# power.net
KiCad netlist of a schematic drawn in Altium Designer
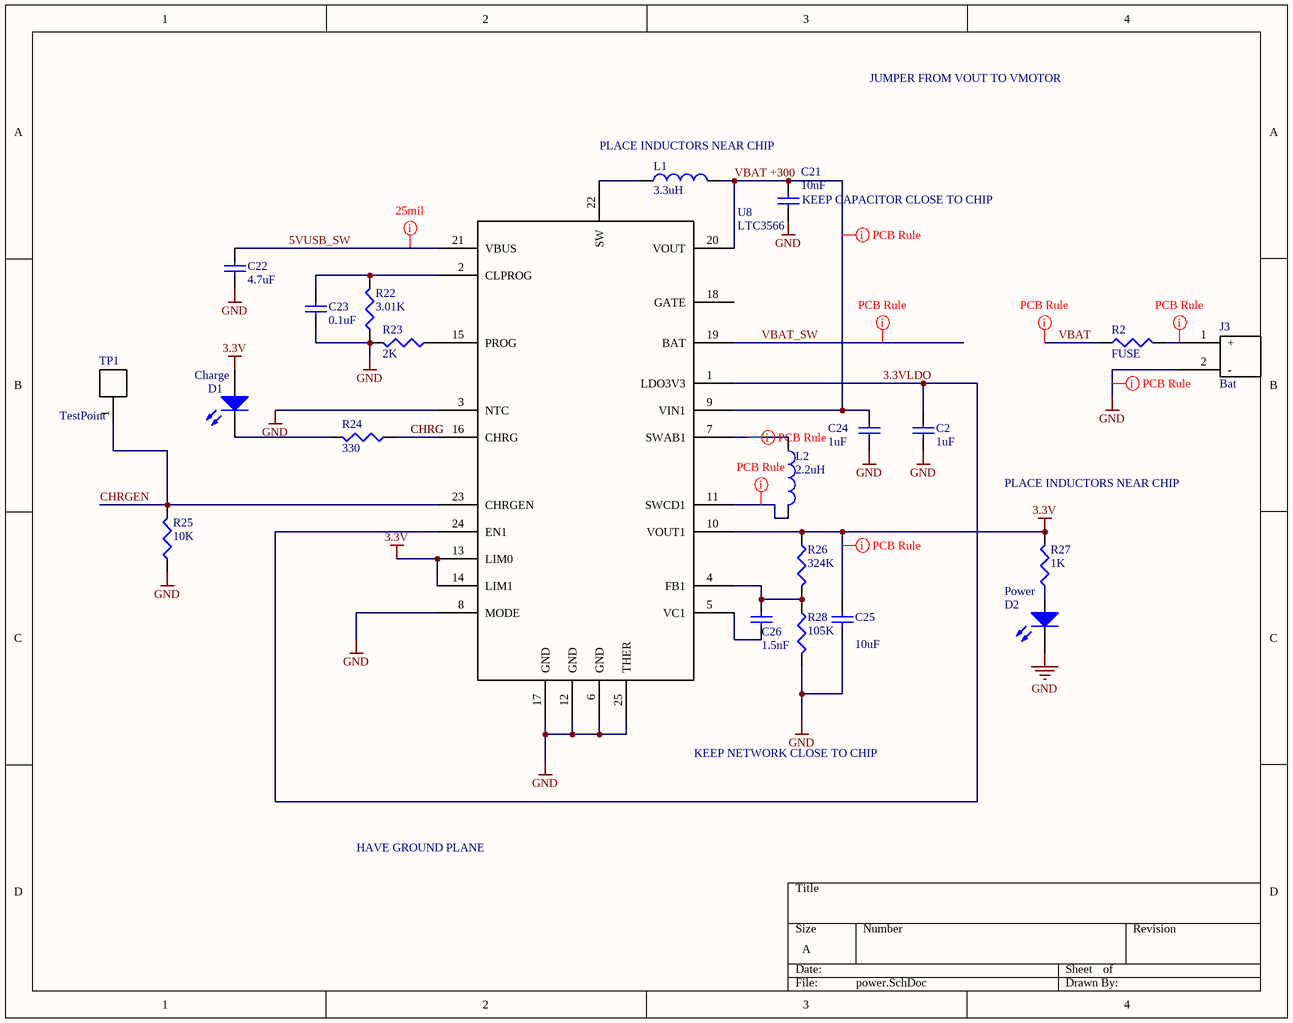
[diagram p0: power.SchDoc]

(export (version "E")
  (design (tool "Eeschema 10.0.6"))
  (components
    (comp (ref "C2")
      (value "1uF")
      (footprint "CAPC1608L")
      (description "Capacitor")
      (fields (field (name "Comment") "Cap") (field (name "PUBLISHER") "Altium Limited"))
      (libsource (lib "Miscellaneous Devices") (part "Cap"))
    )
    (comp (ref "C21")
      (value "10uF")
      (footprint "CAPC1608L")
      (description "Capacitor")
      (fields (field (name "Comment") "Cap") (field (name "PUBLISHER") "Altium Limited"))
      (libsource (lib "Miscellaneous Devices") (part "Cap"))
    )
    (comp (ref "C22")
      (value "4.7uF")
      (footprint "CAPC1608L")
      (description "Capacitor")
      (fields (field (name "Comment") "Cap") (field (name "PUBLISHER") "Altium Limited"))
      (libsource (lib "Miscellaneous Devices") (part "Cap"))
    )
    (comp (ref "C23")
      (value "0.1uF")
      (footprint "CAPC1005L")
      (description "Capacitor")
      (fields (field (name "Comment") "Cap") (field (name "PUBLISHER") "Altium Limited"))
      (libsource (lib "Miscellaneous Devices") (part "Cap"))
    )
    (comp (ref "C24")
      (value "1uF")
      (footprint "CAPC1608L")
      (description "Capacitor")
      (fields (field (name "Comment") "Cap") (field (name "PUBLISHER") "Altium Limited"))
      (libsource (lib "Miscellaneous Devices") (part "Cap"))
    )
    (comp (ref "C25")
      (value "10uF")
      (footprint "CAPC1608L")
      (description "Capacitor")
      (fields (field (name "Comment") "Cap") (field (name "PUBLISHER") "Altium Limited"))
      (libsource (lib "Miscellaneous Devices") (part "Cap"))
    )
    (comp (ref "C26")
      (value "1.5nF")
      (footprint "CAPC1005L")
      (description "Capacitor")
      (fields (field (name "Comment") "Cap") (field (name "PUBLISHER") "Altium Limited"))
      (libsource (lib "Miscellaneous Devices") (part "Cap"))
    )
    (comp (ref "D1")
      (value "Charge")
      (footprint "INDC2012L")
      (description "Typical RED, GREEN, YELLOW, AMBER GaAs LED")
      (fields (field (name "PUBLISHER") "Altium Limited"))
      (libsource (lib "Miscellaneous Devices") (part "LED2"))
    )
    (comp (ref "D2")
      (value "Power")
      (footprint "INDC2012L")
      (description "Typical RED, GREEN, YELLOW, AMBER GaAs LED")
      (fields (field (name "PUBLISHER") "Altium Limited"))
      (libsource (lib "Miscellaneous Devices") (part "LED2"))
    )
    (comp (ref "J3")
      (value "Bat")
      (footprint "BatteryConnJST")
      (libsource (lib "mrone") (part "BatteryConnJST"))
    )
    (comp (ref "L1") (value "3.3uH") (footprint "Inductor-Power") (libsource (lib "mrone") (part "Inductor")))
    (comp (ref "L2") (value "2.2uH") (footprint "Inductor-Power") (libsource (lib "mrone") (part "Inductor")))
    (comp (ref "R2")
      (value "FUSE")
      (footprint "RESC3225L")
      (description "Resistor")
      (fields (field (name "Comment") "Res3") (field (name "PUBLISHER") "Altium Limited"))
      (libsource (lib "Miscellaneous Devices") (part "Res3"))
    )
    (comp (ref "R22")
      (value "3.01K")
      (footprint "RESC1608L")
      (description "Resistor")
      (fields (field (name "Comment") "Res3") (field (name "PUBLISHER") "Altium Limited"))
      (libsource (lib "Miscellaneous Devices") (part "Res3"))
    )
    (comp (ref "R23")
      (value "2K")
      (footprint "RESC1608L")
      (description "Resistor")
      (fields (field (name "Comment") "Res3") (field (name "PUBLISHER") "Altium Limited"))
      (libsource (lib "Miscellaneous Devices") (part "Res3"))
    )
    (comp (ref "R24")
      (value "330")
      (footprint "RESC1608L")
      (description "Resistor")
      (fields (field (name "Comment") "Res3") (field (name "PUBLISHER") "Altium Limited"))
      (libsource (lib "Miscellaneous Devices") (part "Res3"))
    )
    (comp (ref "R25")
      (value "10K")
      (footprint "RESC1608L")
      (description "Resistor")
      (fields (field (name "Comment") "Res3") (field (name "PUBLISHER") "Altium Limited"))
      (libsource (lib "Miscellaneous Devices") (part "Res3"))
    )
    (comp (ref "R26")
      (value "324K")
      (footprint "RESC1608L")
      (description "Resistor")
      (fields (field (name "Comment") "Res3") (field (name "PUBLISHER") "Altium Limited"))
      (libsource (lib "Miscellaneous Devices") (part "Res3"))
    )
    (comp (ref "R27")
      (value "1K")
      (footprint "RESC1608L")
      (description "Resistor")
      (fields (field (name "Comment") "Res3") (field (name "PUBLISHER") "Altium Limited"))
      (libsource (lib "Miscellaneous Devices") (part "Res3"))
    )
    (comp (ref "R28")
      (value "105K")
      (footprint "RESC1608L")
      (description "Resistor")
      (fields (field (name "Comment") "Res3") (field (name "PUBLISHER") "Altium Limited"))
      (libsource (lib "Miscellaneous Devices") (part "Res3"))
    )
    (comp (ref "TP1")
      (value "TestPoint")
      (footprint "TestPoint")
      (libsource (lib "mrone") (part "TestPoint"))
    )
    (comp (ref "U8")
      (value "LTC3566")
      (footprint "QFN-24")
      (libsource (lib "Schematic Components") (part "LTC3566"))
    )
  )
  (nets
    (net (code "1") (name "/3.3VLDO") (class "Default")
      (node (ref "C2") (pin "1") (pinfunction "1_1") (pintype "passive"))
      (node (ref "U8") (pin "1") (pinfunction "LDO3V3_1") (pintype "passive"))
      (node (ref "U8") (pin "24") (pinfunction "EN1_24") (pintype "passive"))
    )
    (net (code "2") (name "/5VUSB_SW") (class "Default")
      (node (ref "C22") (pin "2") (pinfunction "2_2") (pintype "passive"))
      (node (ref "U8") (pin "21") (pinfunction "VBUS_21") (pintype "passive"))
    )
    (net (code "3") (name "/CHRG") (class "Default")
      (node (ref "R24") (pin "1") (pinfunction "1_1") (pintype "passive"))
      (node (ref "U8") (pin "16") (pinfunction "CHRG_16") (pintype "passive"))
    )
    (net (code "4") (name "/CHRGEN") (class "Default")
      (node (ref "R25") (pin "2") (pinfunction "2_2") (pintype "passive"))
      (node (ref "TP1") (pin "1") (pintype "passive"))
      (node (ref "U8") (pin "23") (pinfunction "CHRGEN_23") (pintype "passive"))
    )
    (net (code "5") (name "/VBAT") (class "Default")
      (node (ref "R2") (pin "1") (pinfunction "1_1") (pintype "passive"))
    )
    (net (code "6") (name "/VBAT +300") (class "Default")
      (node (ref "C21") (pin "2") (pinfunction "2_2") (pintype "passive"))
      (node (ref "C24") (pin "1") (pinfunction "1_1") (pintype "passive"))
      (node (ref "L1") (pin "2") (pinfunction "2_2") (pintype "passive"))
      (node (ref "U8") (pin "20") (pinfunction "VOUT_20") (pintype "passive"))
      (node (ref "U8") (pin "9") (pinfunction "VIN1_9") (pintype "passive"))
    )
    (net (code "7") (name "/VBAT_SW") (class "Default")
      (node (ref "U8") (pin "19") (pinfunction "BAT_19") (pintype "passive"))
    )
    (net (code "8") (name "3.3V") (class "Default")
      (node (ref "C25") (pin "2") (pinfunction "2_2") (pintype "passive"))
      (node (ref "D1") (pin "1") (pinfunction "A_1") (pintype "passive"))
      (node (ref "R26") (pin "1") (pinfunction "1_1") (pintype "passive"))
      (node (ref "R27") (pin "2") (pinfunction "2_2") (pintype "passive"))
      (node (ref "U8") (pin "10") (pinfunction "VOUT1_10") (pintype "passive"))
      (node (ref "U8") (pin "13") (pinfunction "LIM0_13") (pintype "passive"))
      (node (ref "U8") (pin "14") (pinfunction "LIM1_14") (pintype "passive"))
    )
    (net (code "9") (name "GND") (class "Default")
      (node (ref "C2") (pin "2") (pinfunction "2_2") (pintype "passive"))
      (node (ref "C21") (pin "1") (pinfunction "1_1") (pintype "passive"))
      (node (ref "C22") (pin "1") (pinfunction "1_1") (pintype "passive"))
      (node (ref "C23") (pin "1") (pinfunction "1_1") (pintype "passive"))
      (node (ref "C24") (pin "2") (pinfunction "2_2") (pintype "passive"))
      (node (ref "C25") (pin "1") (pinfunction "1_1") (pintype "passive"))
      (node (ref "D2") (pin "2") (pinfunction "K_2") (pintype "passive"))
      (node (ref "J3") (pin "2") (pinfunction "-_2") (pintype "passive"))
      (node (ref "R22") (pin "1") (pinfunction "1_1") (pintype "passive"))
      (node (ref "R23") (pin "2") (pinfunction "2_2") (pintype "passive"))
      (node (ref "R25") (pin "1") (pinfunction "1_1") (pintype "passive"))
      (node (ref "R28") (pin "2") (pinfunction "2_2") (pintype "passive"))
      (node (ref "U8") (pin "12") (pinfunction "GND_12") (pintype "passive"))
      (node (ref "U8") (pin "17") (pinfunction "GND_17") (pintype "passive"))
      (node (ref "U8") (pin "25") (pinfunction "THER_25") (pintype "passive"))
      (node (ref "U8") (pin "3") (pinfunction "NTC_3") (pintype "passive"))
      (node (ref "U8") (pin "6") (pinfunction "GND_6") (pintype "passive"))
      (node (ref "U8") (pin "8") (pinfunction "MODE_8") (pintype "passive"))
    )
    (net (code "10") (name "Net-(D1-K)") (class "Default")
      (node (ref "D1") (pin "2") (pinfunction "K_2") (pintype "passive"))
      (node (ref "R24") (pin "2") (pinfunction "2_2") (pintype "passive"))
    )
    (net (code "11") (name "Net-(D2-A)") (class "Default")
      (node (ref "D2") (pin "1") (pinfunction "A_1") (pintype "passive"))
      (node (ref "R27") (pin "1") (pinfunction "1_1") (pintype "passive"))
    )
    (net (code "12") (name "Net-(J3-+)") (class "Default")
      (node (ref "J3") (pin "1") (pinfunction "+_1") (pintype "passive"))
      (node (ref "R2") (pin "2") (pinfunction "2_2") (pintype "passive"))
    )
    (net (code "13") (name "Net-(U8-CLPROG)") (class "Default")
      (node (ref "C23") (pin "2") (pinfunction "2_2") (pintype "passive"))
      (node (ref "R22") (pin "2") (pinfunction "2_2") (pintype "passive"))
      (node (ref "U8") (pin "2") (pinfunction "CLPROG_2") (pintype "passive"))
    )
    (net (code "14") (name "Net-(U8-FB1)") (class "Default")
      (node (ref "C26") (pin "1") (pinfunction "1_1") (pintype "passive"))
      (node (ref "R26") (pin "2") (pinfunction "2_2") (pintype "passive"))
      (node (ref "R28") (pin "1") (pinfunction "1_1") (pintype "passive"))
      (node (ref "U8") (pin "4") (pinfunction "FB1_4") (pintype "passive"))
    )
    (net (code "15") (name "Net-(U8-PROG)") (class "Default")
      (node (ref "R23") (pin "1") (pinfunction "1_1") (pintype "passive"))
      (node (ref "U8") (pin "15") (pinfunction "PROG_15") (pintype "passive"))
    )
    (net (code "16") (name "Net-(U8-SW)") (class "Default")
      (node (ref "L1") (pin "1") (pinfunction "1_1") (pintype "passive"))
      (node (ref "U8") (pin "22") (pinfunction "SW_22") (pintype "passive"))
    )
    (net (code "17") (name "Net-(U8-SWAB1)") (class "Default")
      (node (ref "L2") (pin "1") (pinfunction "1_1") (pintype "passive"))
      (node (ref "U8") (pin "7") (pinfunction "SWAB1_7") (pintype "passive"))
    )
    (net (code "18") (name "Net-(U8-SWCD1)") (class "Default")
      (node (ref "L2") (pin "2") (pinfunction "2_2") (pintype "passive"))
      (node (ref "U8") (pin "11") (pinfunction "SWCD1_11") (pintype "passive"))
    )
    (net (code "19") (name "Net-(U8-VC1)") (class "Default")
      (node (ref "C26") (pin "2") (pinfunction "2_2") (pintype "passive"))
      (node (ref "U8") (pin "5") (pinfunction "VC1_5") (pintype "passive"))
    )
    (net (code "20") (name "unconnected-(U8-GATE-Pad18)") (class "Default")
      (node (ref "U8") (pin "18") (pinfunction "GATE_18") (pintype "passive"))
    )
  )
)
